# kd_inz_supply.net
KiCad netlist of a schematic drawn in Altium Designer
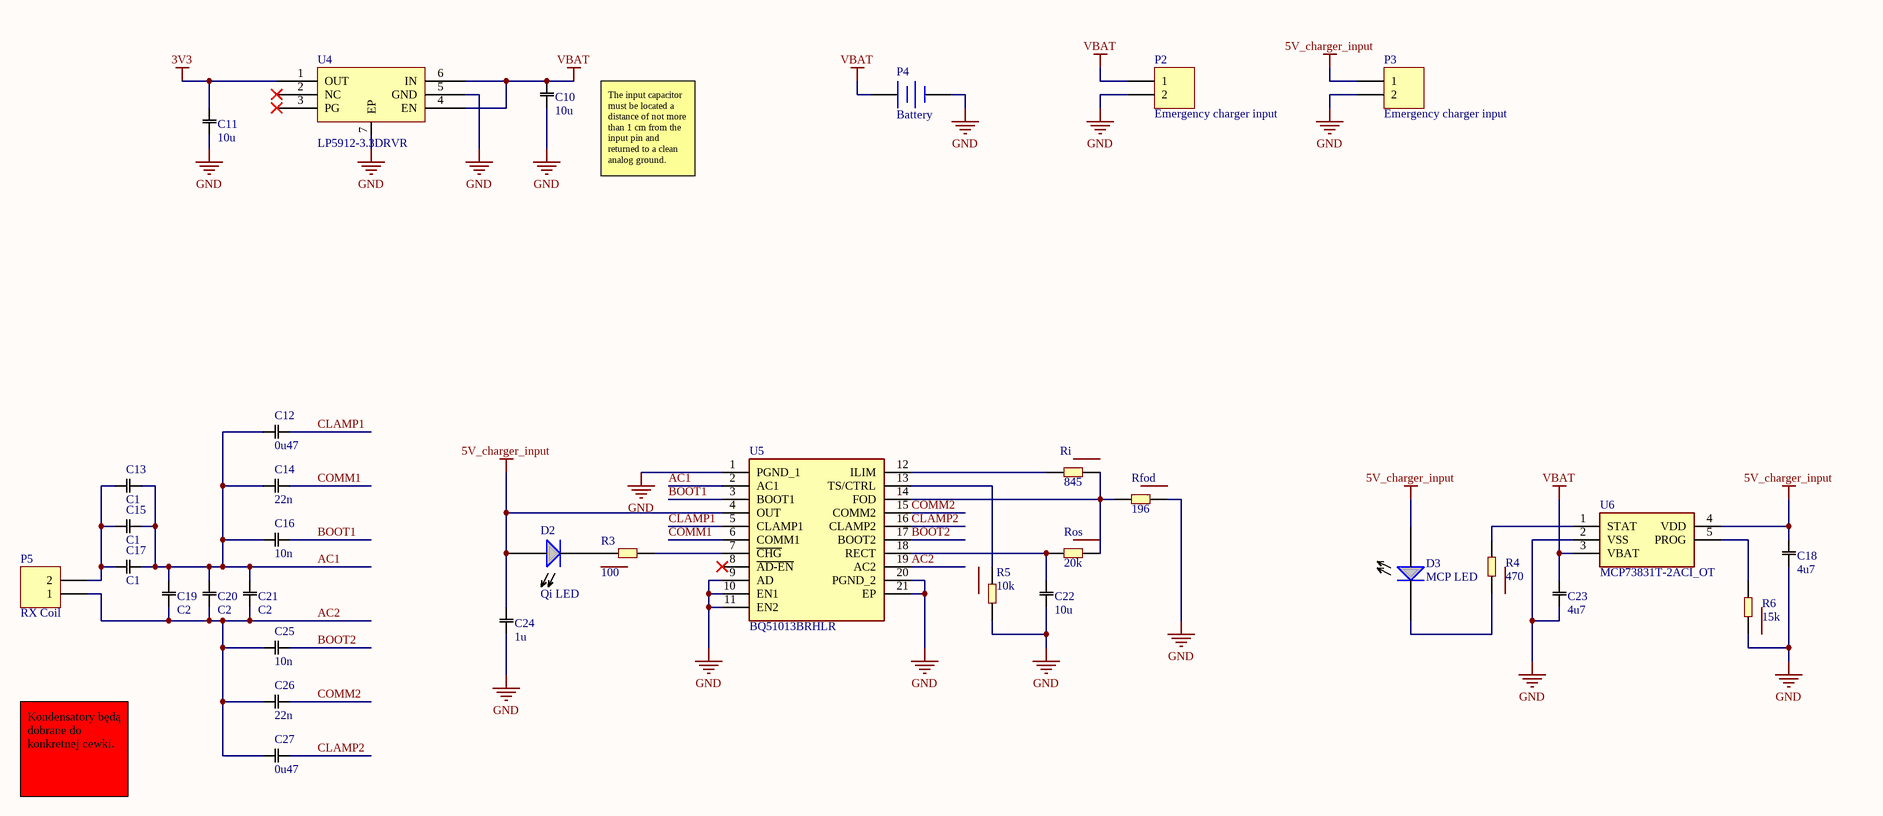
[diagram p0: kd_inz_supply.SchDoc]

(export (version "E")
  (design (tool "Eeschema 10.0.6"))
  (components
    (comp (ref "C10")
      (value "10u")
      (footprint "0402")
      (description "Capacitor")
      (libsource (lib "basic_lib_v1-2") (part "C"))
    )
    (comp (ref "C11")
      (value "10u")
      (footprint "0402")
      (description "Capacitor")
      (libsource (lib "basic_lib_v1-2") (part "C"))
    )
    (comp (ref "C12")
      (value "0u47")
      (footprint "0402")
      (description "Capacitor")
      (libsource (lib "basic_lib_v1-2") (part "C"))
    )
    (comp (ref "C13")
      (value "C1")
      (footprint "0402")
      (description "Capacitor")
      (libsource (lib "basic_lib_v1-2") (part "C"))
    )
    (comp (ref "C14")
      (value "22n")
      (footprint "0402")
      (description "Capacitor")
      (libsource (lib "basic_lib_v1-2") (part "C"))
    )
    (comp (ref "C15")
      (value "C1")
      (footprint "0402")
      (description "Capacitor")
      (libsource (lib "basic_lib_v1-2") (part "C"))
    )
    (comp (ref "C16")
      (value "10n")
      (footprint "0402")
      (description "Capacitor")
      (libsource (lib "basic_lib_v1-2") (part "C"))
    )
    (comp (ref "C17")
      (value "C1")
      (footprint "0402")
      (description "Capacitor")
      (libsource (lib "basic_lib_v1-2") (part "C"))
    )
    (comp (ref "C18")
      (value "4u7")
      (footprint "0402")
      (description "Capacitor")
      (libsource (lib "basic_lib_v1-2") (part "C"))
    )
    (comp (ref "C19")
      (value "C2")
      (footprint "0402")
      (description "Capacitor")
      (libsource (lib "basic_lib_v1-2") (part "C"))
    )
    (comp (ref "C20")
      (value "C2")
      (footprint "0402")
      (description "Capacitor")
      (libsource (lib "basic_lib_v1-2") (part "C"))
    )
    (comp (ref "C21")
      (value "C2")
      (footprint "0402")
      (description "Capacitor")
      (libsource (lib "basic_lib_v1-2") (part "C"))
    )
    (comp (ref "C22")
      (value "10u")
      (footprint "0402")
      (description "Capacitor")
      (libsource (lib "basic_lib_v1-2") (part "C"))
    )
    (comp (ref "C23")
      (value "4u7")
      (footprint "0402")
      (description "Capacitor")
      (libsource (lib "basic_lib_v1-2") (part "C"))
    )
    (comp (ref "C24")
      (value "1u")
      (footprint "0402")
      (description "Capacitor")
      (libsource (lib "basic_lib_v1-2") (part "C"))
    )
    (comp (ref "C25")
      (value "10n")
      (footprint "0402")
      (description "Capacitor")
      (libsource (lib "basic_lib_v1-2") (part "C"))
    )
    (comp (ref "C26")
      (value "22n")
      (footprint "0402")
      (description "Capacitor")
      (libsource (lib "basic_lib_v1-2") (part "C"))
    )
    (comp (ref "C27")
      (value "0u47")
      (footprint "0402")
      (description "Capacitor")
      (libsource (lib "basic_lib_v1-2") (part "C"))
    )
    (comp (ref "D2") (value "Qi LED") (footprint "0402") (libsource (lib "basic_lib_v1-2") (part "LED")))
    (comp (ref "D3") (value "MCP LED") (footprint "0402") (libsource (lib "basic_lib_v1-2") (part "LED")))
    (comp (ref "P2")
      (value "Emergency charger input")
      (footprint "HDR1X2")
      (description "Header, 2-Pin")
      (fields (field (name "PUBLISHER") "Altium Limited"))
      (libsource (lib "Miscellaneous Connectors") (part "Header 2"))
    )
    (comp (ref "P3")
      (value "Emergency charger input")
      (footprint "HDR1X2")
      (description "Header, 2-Pin")
      (fields (field (name "PUBLISHER") "Altium Limited"))
      (libsource (lib "Miscellaneous Connectors") (part "Header 2"))
    )
    (comp (ref "P4")
      (value "Battery")
      (footprint "BAT-2")
      (description "Multicell Battery")
      (fields (field (name "PUBLISHER") "Altium Limited"))
      (libsource (lib "Miscellaneous Devices") (part "Battery"))
    )
    (comp (ref "P5")
      (value "RX Coil")
      (footprint "HDR1X2")
      (description "Header, 2-Pin")
      (fields (field (name "PUBLISHER") "Altium Limited"))
      (libsource (lib "") (part "Header 2_1"))
    )
    (comp (ref "R3")
      (value "100")
      (footprint "0402")
      (description "Resistor")
      (libsource (lib "") (part "R_1"))
    )
    (comp (ref "R4")
      (value "470")
      (footprint "0402")
      (description "Resistor")
      (libsource (lib "") (part "R_3"))
    )
    (comp (ref "R5")
      (value "10k")
      (footprint "0402")
      (description "Resistor")
      (libsource (lib "") (part "R_2"))
    )
    (comp (ref "R6")
      (value "15k")
      (footprint "0402")
      (description "Resistor")
      (libsource (lib "") (part "R_3"))
    )
    (comp (ref "Rfod")
      (value "196")
      (footprint "0402")
      (description "Resistor")
      (libsource (lib "basic_lib_v1-2") (part "R"))
    )
    (comp (ref "Ri")
      (value "845")
      (footprint "0402")
      (description "Resistor")
      (libsource (lib "basic_lib_v1-2") (part "R"))
    )
    (comp (ref "Ros")
      (value "20k")
      (footprint "0402")
      (description "Resistor")
      (libsource (lib "basic_lib_v1-2") (part "R"))
    )
    (comp (ref "U4")
      (value "LP5912-3.3DRVR")
      (footprint "WSON-6")
      (libsource (lib "basic_lib_v1-2") (part "LP5912"))
    )
    (comp (ref "U5")
      (value "BQ51013BRHLR")
      (footprint "kd_lib:BQ51050BRHLR")
      (description "Integrated Circuit")
      (fields (field (name "MOUSER PART NUMBER") "595-BQ51013BRHLR"))
      (libsource (lib "kd_lib") (part "BQ51013BRHLR"))
    )
    (comp (ref "U6")
      (value "MCP73831T-2ACI_OT")
      (footprint "kd_lib:SOT95P270X145-5N")
      (description "Integrated Circuit")
      (fields
        (field (name "MANUFACTURER_PART_NUMBER") "MCP73831T-2ACI/OT")
        (field (name "MOUSER PART NUMBER") "579-MCP73831T-2ACIOT")
      )
      (libsource (lib "kd_lib") (part "MCP73831T-2ACI_OT"))
    )
  )
  (nets
    (net (code "1") (name "/AC1") (class "Default")
      (node (ref "C12") (pin "2") (pintype "passive"))
      (node (ref "C13") (pin "2") (pintype "passive"))
      (node (ref "C14") (pin "1") (pintype "passive"))
      (node (ref "C15") (pin "2") (pintype "passive"))
      (node (ref "C16") (pin "1") (pintype "passive"))
      (node (ref "C17") (pin "2") (pintype "passive"))
      (node (ref "C19") (pin "2") (pintype "passive"))
      (node (ref "C20") (pin "2") (pintype "passive"))
      (node (ref "C21") (pin "2") (pintype "passive"))
      (node (ref "U5") (pin "2") (pinfunction "AC1_2") (pintype "passive"))
    )
    (net (code "2") (name "/AC2") (class "Default")
      (node (ref "C19") (pin "1") (pintype "passive"))
      (node (ref "C20") (pin "1") (pintype "passive"))
      (node (ref "C21") (pin "1") (pintype "passive"))
      (node (ref "C25") (pin "1") (pintype "passive"))
      (node (ref "C26") (pin "1") (pintype "passive"))
      (node (ref "C27") (pin "1") (pintype "passive"))
      (node (ref "P5") (pin "1") (pinfunction "1_1") (pintype "passive"))
      (node (ref "U5") (pin "19") (pinfunction "AC2_19") (pintype "passive"))
    )
    (net (code "3") (name "/BOOT1") (class "Default")
      (node (ref "C16") (pin "2") (pintype "passive"))
      (node (ref "U5") (pin "3") (pinfunction "BOOT1_3") (pintype "passive"))
    )
    (net (code "4") (name "/BOOT2") (class "Default")
      (node (ref "C25") (pin "2") (pintype "passive"))
      (node (ref "U5") (pin "17") (pinfunction "BOOT2_17") (pintype "passive"))
    )
    (net (code "5") (name "/CLAMP1") (class "Default")
      (node (ref "C12") (pin "1") (pintype "passive"))
      (node (ref "U5") (pin "5") (pinfunction "CLAMP1_5") (pintype "passive"))
    )
    (net (code "6") (name "/CLAMP2") (class "Default")
      (node (ref "C27") (pin "2") (pintype "passive"))
      (node (ref "U5") (pin "16") (pinfunction "CLAMP2_16") (pintype "passive"))
    )
    (net (code "7") (name "/COMM1") (class "Default")
      (node (ref "C14") (pin "2") (pintype "passive"))
      (node (ref "U5") (pin "6") (pinfunction "COMM1_6") (pintype "passive"))
    )
    (net (code "8") (name "/COMM2") (class "Default")
      (node (ref "C26") (pin "2") (pintype "passive"))
      (node (ref "U5") (pin "15") (pinfunction "COMM2_15") (pintype "passive"))
    )
    (net (code "9") (name "3V3") (class "Default")
      (node (ref "C11") (pin "2") (pintype "passive"))
      (node (ref "U4") (pin "1") (pinfunction "OUT_1") (pintype "passive"))
    )
    (net (code "10") (name "5V_charger_input") (class "Default")
      (node (ref "C18") (pin "2") (pintype "passive"))
      (node (ref "C24") (pin "2") (pintype "passive"))
      (node (ref "D2") (pin "2") (pinfunction "2_2") (pintype "passive"))
      (node (ref "D3") (pin "2") (pinfunction "2_2") (pintype "passive"))
      (node (ref "P3") (pin "1") (pinfunction "1_1") (pintype "passive"))
      (node (ref "U5") (pin "4") (pinfunction "OUT_4") (pintype "passive"))
      (node (ref "U6") (pin "4") (pinfunction "VDD_4") (pintype "passive"))
    )
    (net (code "11") (name "GND") (class "Default")
      (node (ref "C10") (pin "1") (pintype "passive"))
      (node (ref "C11") (pin "1") (pintype "passive"))
      (node (ref "C18") (pin "1") (pintype "passive"))
      (node (ref "C22") (pin "1") (pintype "passive"))
      (node (ref "C23") (pin "1") (pintype "passive"))
      (node (ref "C24") (pin "1") (pintype "passive"))
      (node (ref "P2") (pin "2") (pinfunction "2_2") (pintype "passive"))
      (node (ref "P3") (pin "2") (pinfunction "2_2") (pintype "passive"))
      (node (ref "P4") (pin "2") (pinfunction "-_2") (pintype "passive"))
      (node (ref "R5") (pin "1") (pintype "passive"))
      (node (ref "R6") (pin "2") (pintype "passive"))
      (node (ref "Rfod") (pin "2") (pintype "passive"))
      (node (ref "U4") (pin "5") (pinfunction "GND_5") (pintype "passive"))
      (node (ref "U4") (pin "7") (pinfunction "EP_7") (pintype "passive"))
      (node (ref "U5") (pin "1") (pinfunction "PGND_1_1") (pintype "passive"))
      (node (ref "U5") (pin "10") (pinfunction "EN1_10") (pintype "passive"))
      (node (ref "U5") (pin "11") (pinfunction "EN2_11") (pintype "passive"))
      (node (ref "U5") (pin "20") (pinfunction "PGND_2_20") (pintype "passive"))
      (node (ref "U5") (pin "21") (pinfunction "EP_21") (pintype "passive"))
      (node (ref "U5") (pin "9") (pinfunction "AD_9") (pintype "passive"))
      (node (ref "U6") (pin "2") (pinfunction "VSS_2") (pintype "passive"))
    )
    (net (code "12") (name "Net-(C13-Pad1)") (class "Default")
      (node (ref "C13") (pin "1") (pintype "passive"))
      (node (ref "C15") (pin "1") (pintype "passive"))
      (node (ref "C17") (pin "1") (pintype "passive"))
      (node (ref "P5") (pin "2") (pinfunction "2_2") (pintype "passive"))
    )
    (net (code "13") (name "Net-(D2-Pad1)") (class "Default")
      (node (ref "D2") (pin "1") (pinfunction "1_1") (pintype "passive"))
      (node (ref "R3") (pin "2") (pintype "passive"))
    )
    (net (code "14") (name "Net-(D3-Pad1)") (class "Default")
      (node (ref "D3") (pin "1") (pinfunction "1_1") (pintype "passive"))
      (node (ref "R4") (pin "2") (pintype "passive"))
    )
    (net (code "15") (name "Net-(U5-FOD)") (class "Default")
      (node (ref "Rfod") (pin "1") (pintype "passive"))
      (node (ref "Ri") (pin "2") (pintype "passive"))
      (node (ref "Ros") (pin "2") (pintype "passive"))
      (node (ref "U5") (pin "14") (pinfunction "FOD_14") (pintype "passive"))
    )
    (net (code "16") (name "Net-(U5-ILIM)") (class "Default")
      (node (ref "Ri") (pin "1") (pintype "passive"))
      (node (ref "U5") (pin "12") (pinfunction "ILIM_12") (pintype "passive"))
    )
    (net (code "17") (name "Net-(U5-RECT)") (class "Default")
      (node (ref "C22") (pin "2") (pintype "passive"))
      (node (ref "Ros") (pin "1") (pintype "passive"))
      (node (ref "U5") (pin "18") (pinfunction "RECT_18") (pintype "passive"))
    )
    (net (code "18") (name "Net-(U5-TS{slash}CTRL)") (class "Default")
      (node (ref "R5") (pin "2") (pintype "passive"))
      (node (ref "U5") (pin "13") (pinfunction "TS/CTRL_13") (pintype "passive"))
    )
    (net (code "19") (name "Net-(U5-~{CHG})") (class "Default")
      (node (ref "R3") (pin "1") (pintype "passive"))
      (node (ref "U5") (pin "7") (pinfunction "~{CHG}_7") (pintype "passive"))
    )
    (net (code "20") (name "Net-(U6-PROG)") (class "Default")
      (node (ref "R6") (pin "1") (pintype "passive"))
      (node (ref "U6") (pin "5") (pinfunction "PROG_5") (pintype "passive"))
    )
    (net (code "21") (name "Net-(U6-STAT)") (class "Default")
      (node (ref "R4") (pin "1") (pintype "passive"))
      (node (ref "U6") (pin "1") (pinfunction "STAT_1") (pintype "passive"))
    )
    (net (code "22") (name "VBAT") (class "Default")
      (node (ref "C10") (pin "2") (pintype "passive"))
      (node (ref "C23") (pin "2") (pintype "passive"))
      (node (ref "P2") (pin "1") (pinfunction "1_1") (pintype "passive"))
      (node (ref "P4") (pin "1") (pinfunction "+_1") (pintype "passive"))
      (node (ref "U4") (pin "4") (pinfunction "EN_4") (pintype "passive"))
      (node (ref "U4") (pin "6") (pinfunction "IN_6") (pintype "passive"))
      (node (ref "U6") (pin "3") (pinfunction "VBAT_3") (pintype "passive"))
    )
    (net (code "23") (name "unconnected-(U4-NC-Pad2)") (class "Default")
      (node (ref "U4") (pin "2") (pinfunction "NC_2") (pintype "passive+no_connect"))
    )
    (net (code "24") (name "unconnected-(U4-PG-Pad3)") (class "Default")
      (node (ref "U4") (pin "3") (pinfunction "PG_3") (pintype "passive+no_connect"))
    )
    (net (code "25") (name "unconnected-(U5-~{AD-EN}-Pad8)") (class "Default")
      (node (ref "U5") (pin "8") (pinfunction "~{AD-EN}_8") (pintype "passive+no_connect"))
    )
  )
)
